# FOC_Lite.net
KiCad netlist of a schematic drawn in Altium Designer
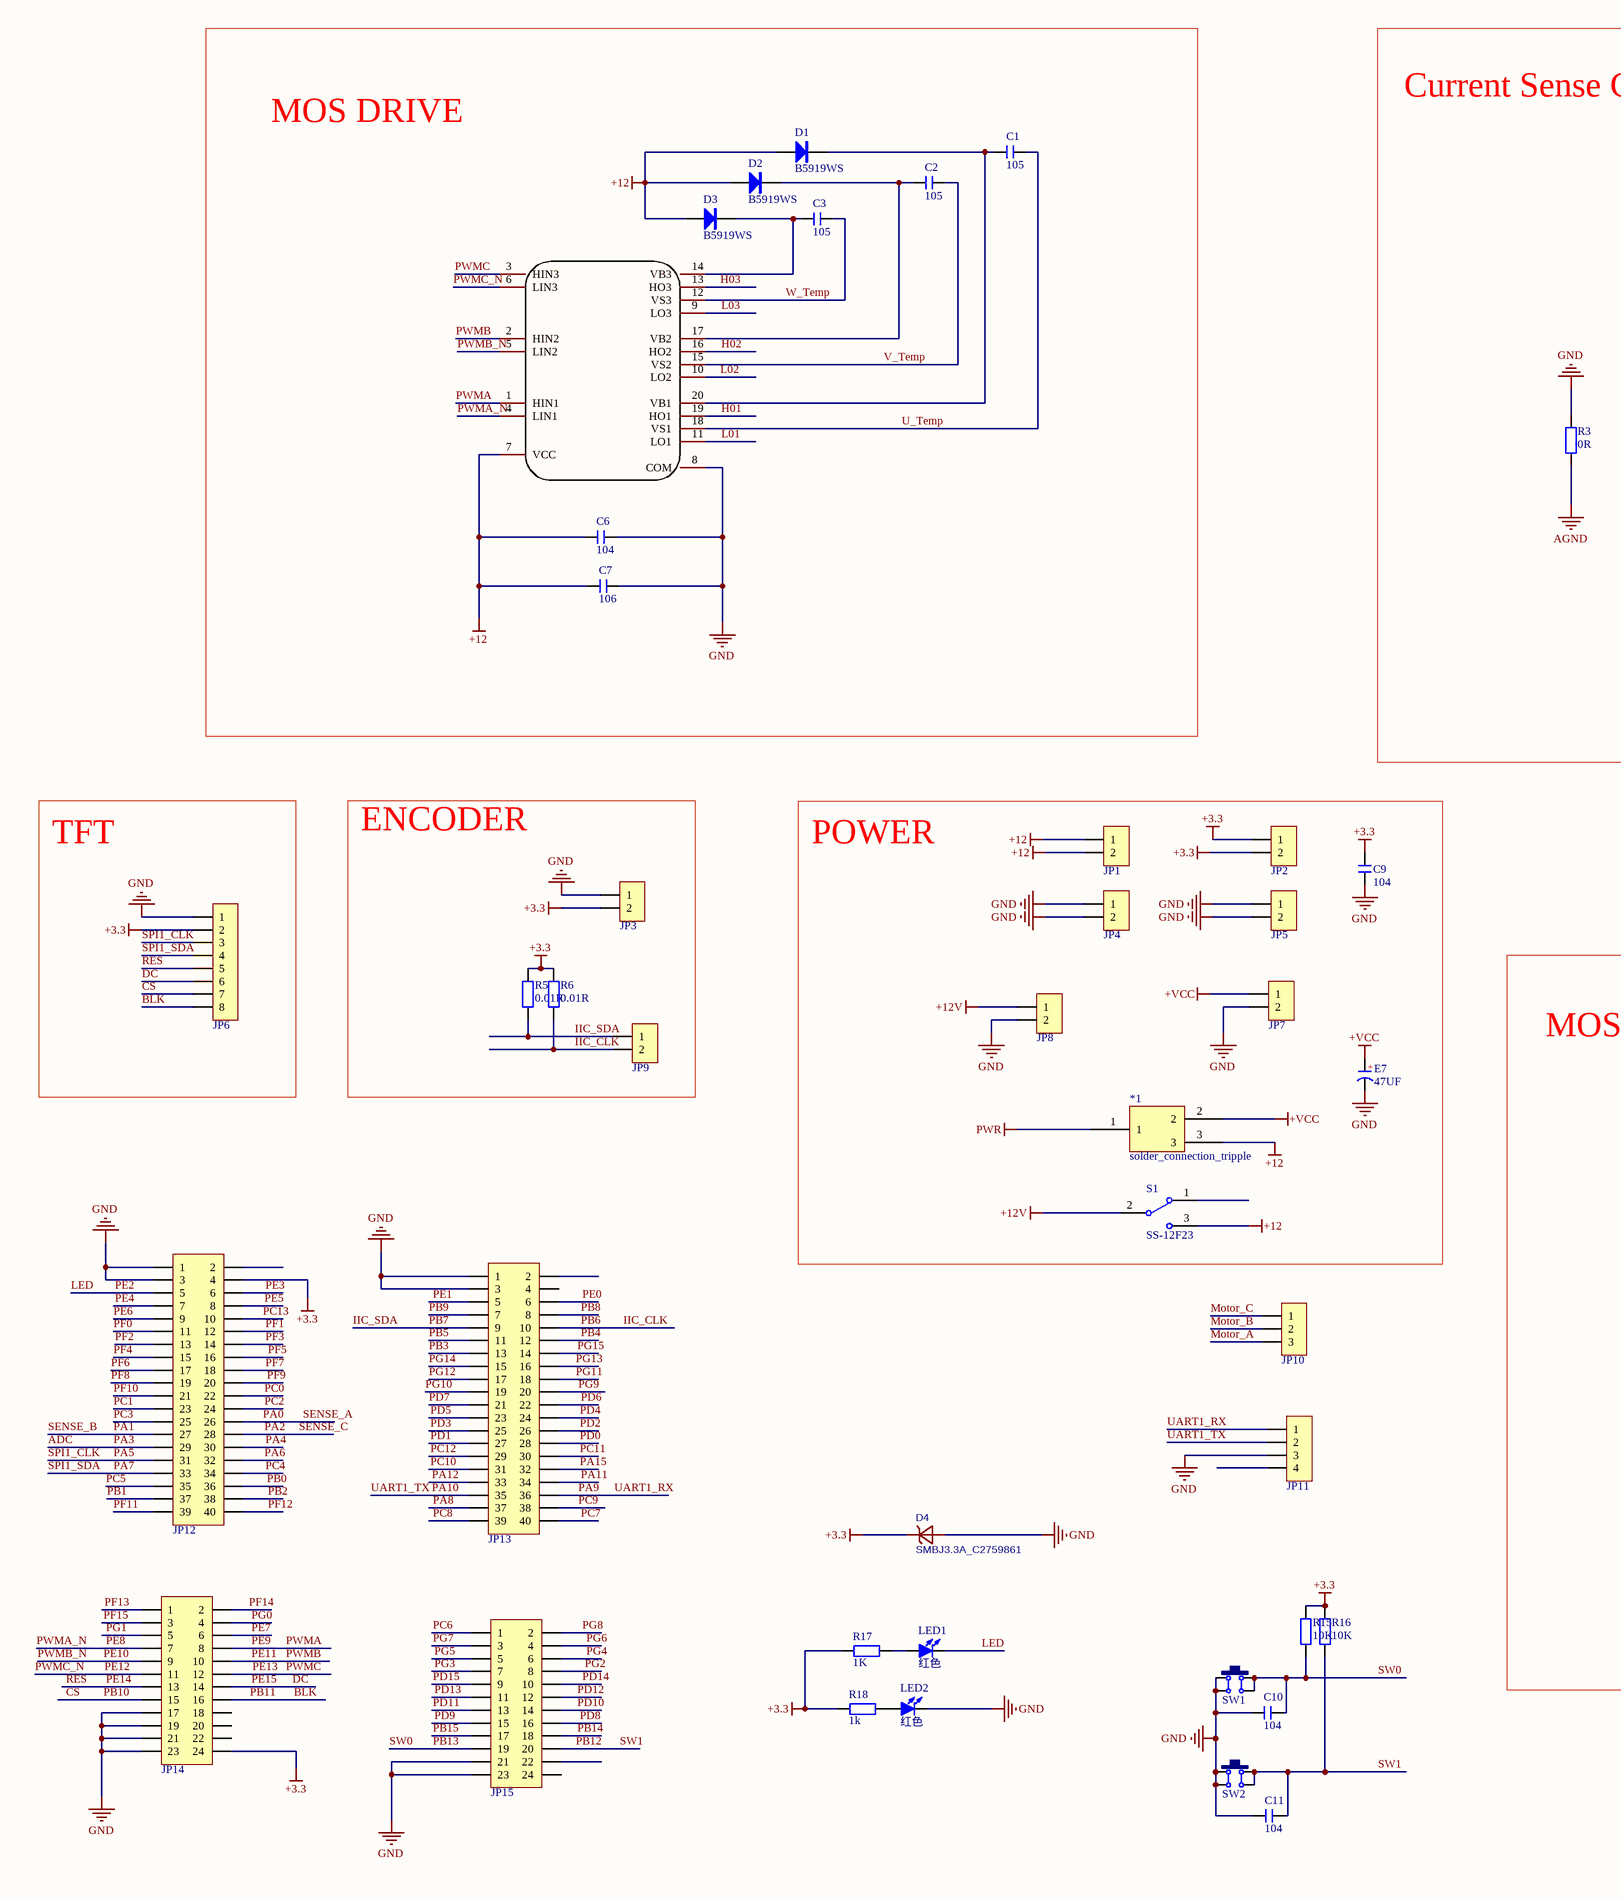
[diagram p0: FOC_Lite.SchDoc, left]
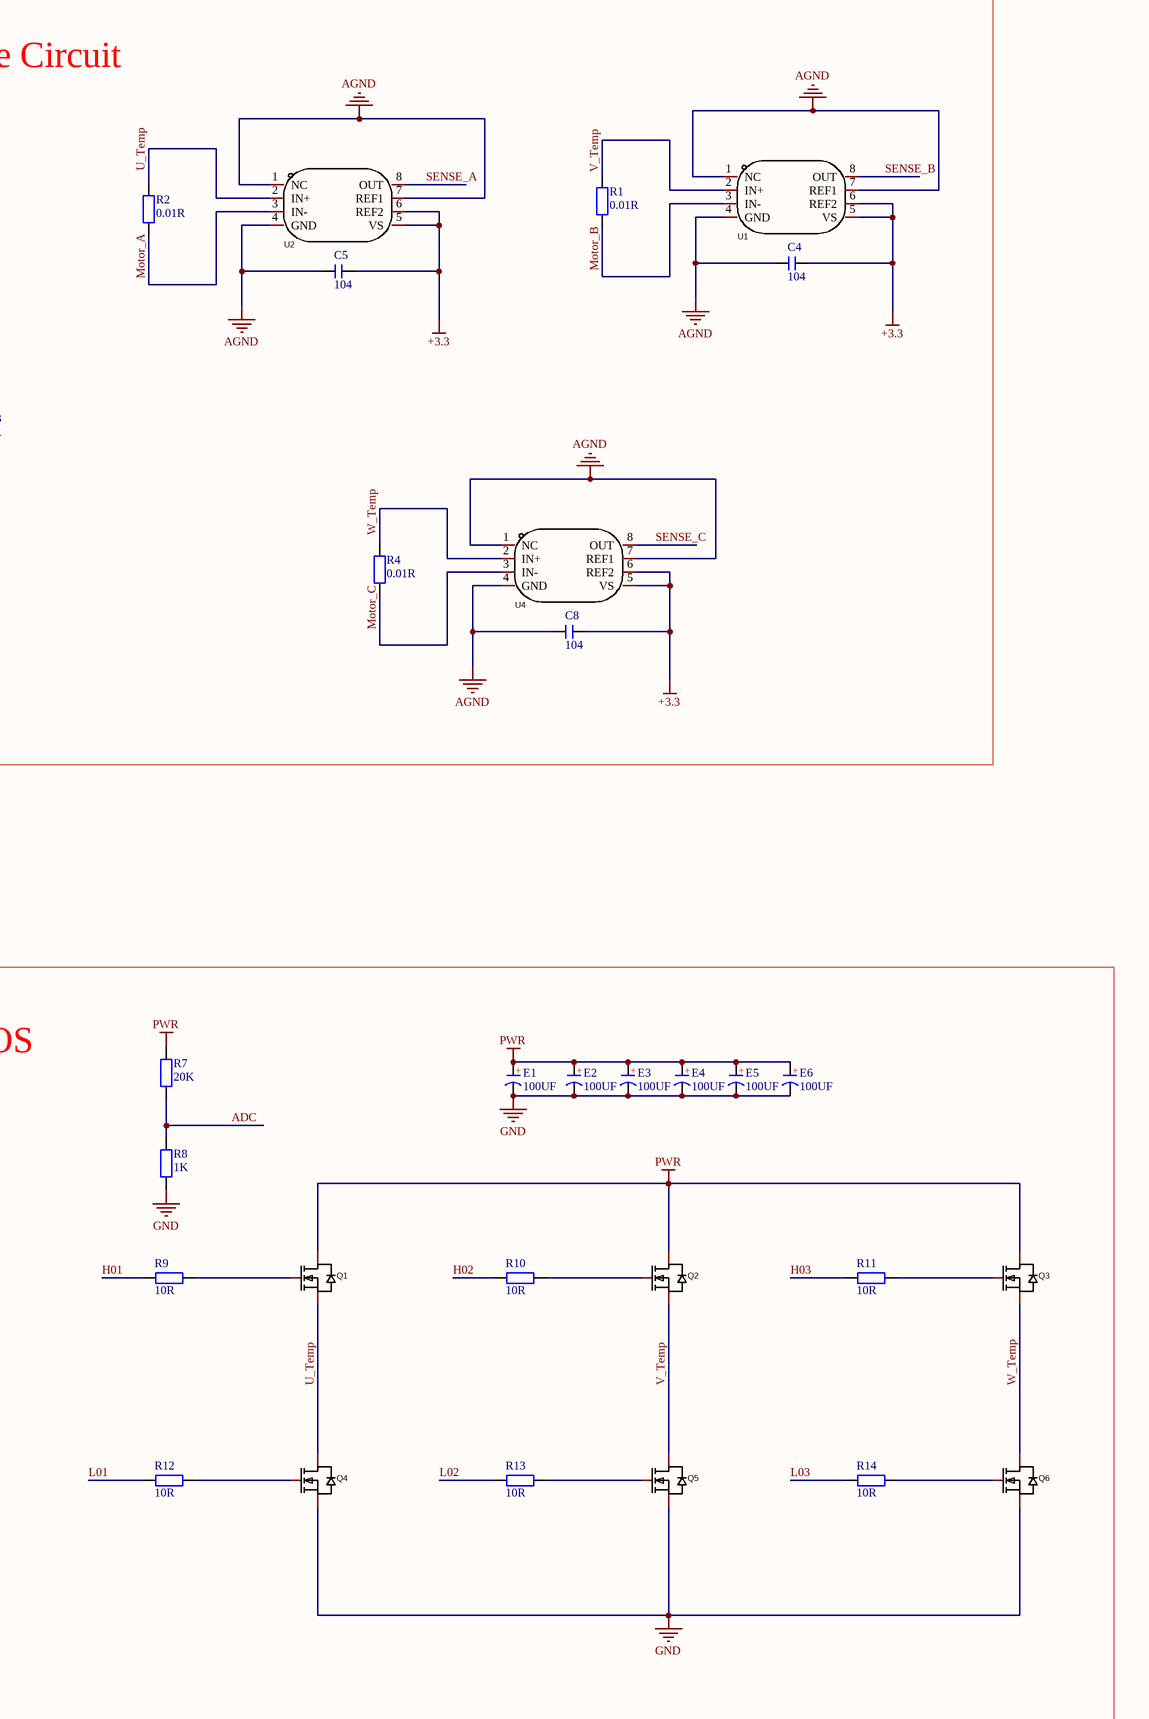
[diagram p1: FOC_Lite.SchDoc, right]

(export (version "E")
  (design (tool "Eeschema 10.0.6"))
  (components
    (comp (ref "*1")
      (value "solder_connection_tripple")
      (footprint "solder_connection_tripple_big")
      (libsource (lib "常见模块2") (part "solder_connection_tripple"))
    )
    (comp (ref "C1")
      (value "105")
      (footprint "C 0805")
      (description "无极性贴片电容")
      (fields (field (name "版权归属") "黎明电子style"))
      (libsource (lib "1.3.2-电阻_电容_电感") (part "C"))
    )
    (comp (ref "C2")
      (value "105")
      (footprint "C 0805")
      (description "无极性贴片电容")
      (fields (field (name "版权归属") "黎明电子style"))
      (libsource (lib "1.3.2-电阻_电容_电感") (part "C"))
    )
    (comp (ref "C3")
      (value "105")
      (footprint "C 0805")
      (description "无极性贴片电容")
      (fields (field (name "版权归属") "黎明电子style"))
      (libsource (lib "1.3.2-电阻_电容_电感") (part "C"))
    )
    (comp (ref "C4")
      (value "104")
      (footprint "C 0805")
      (description "无极性贴片电容")
      (fields (field (name "版权归属") "黎明电子style"))
      (libsource (lib "1.3.2-电阻_电容_电感") (part "C"))
    )
    (comp (ref "C5")
      (value "104")
      (footprint "C 0805")
      (description "无极性贴片电容")
      (fields (field (name "版权归属") "黎明电子style"))
      (libsource (lib "1.3.2-电阻_电容_电感") (part "C"))
    )
    (comp (ref "C6")
      (value "104")
      (footprint "C 0805")
      (description "无极性贴片电容")
      (fields (field (name "版权归属") "黎明电子style"))
      (libsource (lib "1.3.2-电阻_电容_电感") (part "C"))
    )
    (comp (ref "C7")
      (value "106")
      (footprint "C 0805")
      (description "无极性贴片电容")
      (fields (field (name "版权归属") "黎明电子style"))
      (libsource (lib "1.3.2-电阻_电容_电感") (part "C"))
    )
    (comp (ref "C8")
      (value "104")
      (footprint "C 0805")
      (description "无极性贴片电容")
      (fields (field (name "版权归属") "黎明电子style"))
      (libsource (lib "1.3.2-电阻_电容_电感") (part "C"))
    )
    (comp (ref "C9")
      (value "104")
      (footprint "C 0805")
      (description "无极性贴片电容")
      (fields (field (name "版权归属") "黎明电子style"))
      (libsource (lib "1.3.2-电阻_电容_电感") (part "C"))
    )
    (comp (ref "C10")
      (value "104")
      (footprint "C 0603")
      (description "无极性贴片电容")
      (fields (field (name "版权归属") "黎明电子style"))
      (libsource (lib "1.3.2-电阻_电容_电感") (part "C"))
    )
    (comp (ref "C11")
      (value "104")
      (footprint "C 0603")
      (description "无极性贴片电容")
      (fields (field (name "版权归属") "黎明电子style"))
      (libsource (lib "1.3.2-电阻_电容_电感") (part "C"))
    )
    (comp (ref "D1")
      (value "B5919WS")
      (footprint "SOD-323")
      (description "肖特基二极管")
      (fields (field (name "版权归属") "源创客"))
      (libsource (lib "1.3.3-二极管_整流桥") (part "1N5819"))
    )
    (comp (ref "D2")
      (value "B5919WS")
      (footprint "SOD-323")
      (description "肖特基二极管")
      (fields (field (name "版权归属") "源创客"))
      (libsource (lib "1.3.3-二极管_整流桥") (part "1N5819"))
    )
    (comp (ref "D3")
      (value "B5919WS")
      (footprint "SOD-323")
      (description "肖特基二极管")
      (fields (field (name "版权归属") "源创客"))
      (libsource (lib "1.3.3-二极管_整流桥") (part "1N5819"))
    )
    (comp (ref "D4")
      (value "SMBJ3.3A_C2759861")
      (footprint "SMB3.3A")
      (fields
        (field (name "BOM_SUPPLIER PART") "C2759861")
        (field (name "BOM_MANUFACTURER PART") "SMBJ3.3A")
        (field (name "CONTRIBUTOR") "LCSC")
      )
      (libsource (lib "常见模块") (part "SMBJ3.3A_C2759861"))
    )
    (comp (ref "E1")
      (value "100UF")
      (footprint "CD D(7343)")
      (description "贴片钽电容")
      (fields (field (name "版权归属") "黎明电子style"))
      (libsource (lib "1.3.2-电阻_电容_电感") (part "C-CD"))
    )
    (comp (ref "E2")
      (value "100UF")
      (footprint "CD D(7343)")
      (description "贴片钽电容")
      (fields (field (name "版权归属") "黎明电子style"))
      (libsource (lib "1.3.2-电阻_电容_电感") (part "C-CD"))
    )
    (comp (ref "E3")
      (value "100UF")
      (footprint "CD D(7343)")
      (description "贴片钽电容")
      (fields (field (name "版权归属") "黎明电子style"))
      (libsource (lib "1.3.2-电阻_电容_电感") (part "C-CD"))
    )
    (comp (ref "E4")
      (value "100UF")
      (footprint "CD D(7343)")
      (description "贴片钽电容")
      (fields (field (name "版权归属") "黎明电子style"))
      (libsource (lib "1.3.2-电阻_电容_电感") (part "C-CD"))
    )
    (comp (ref "E5")
      (value "100UF")
      (footprint "CD D(7343)")
      (description "贴片钽电容")
      (fields (field (name "版权归属") "黎明电子style"))
      (libsource (lib "1.3.2-电阻_电容_电感") (part "C-CD"))
    )
    (comp (ref "E6")
      (value "100UF")
      (footprint "CD D(7343)")
      (description "贴片钽电容")
      (fields (field (name "版权归属") "黎明电子style"))
      (libsource (lib "1.3.2-电阻_电容_电感") (part "C-CD"))
    )
    (comp (ref "E7")
      (value "47UF")
      (footprint "CD D(7343)")
      (description "贴片钽电容")
      (fields (field (name "版权归属") "黎明电子style"))
      (libsource (lib "1.3.2-电阻_电容_电感") (part "C-CD"))
    )
    (comp (ref "JP1")
      (value "HDR-1X2")
      (footprint "HDR-1X2")
      (description "2P接插件")
      (fields (field (name "版权归属") "黎明电子style"))
      (libsource (lib "1.5.1-接插件") (part "Header 2"))
    )
    (comp (ref "JP2")
      (value "HDR-1X2")
      (footprint "HDR-1X2")
      (description "2P接插件")
      (fields (field (name "版权归属") "黎明电子style"))
      (libsource (lib "1.5.1-接插件") (part "Header 2"))
    )
    (comp (ref "JP3")
      (value "HDR-1X2")
      (footprint "HDR-1X2")
      (description "2P接插件")
      (fields (field (name "版权归属") "黎明电子style"))
      (libsource (lib "1.5.1-接插件") (part "Header 2"))
    )
    (comp (ref "JP4")
      (value "HDR-1X2")
      (footprint "HDR-1X2")
      (description "2P接插件")
      (fields (field (name "版权归属") "黎明电子style"))
      (libsource (lib "1.5.1-接插件") (part "Header 2"))
    )
    (comp (ref "JP5")
      (value "HDR-1X2")
      (footprint "HDR-1X2")
      (description "2P接插件")
      (fields (field (name "版权归属") "黎明电子style"))
      (libsource (lib "1.5.1-接插件") (part "Header 2"))
    )
    (comp (ref "JP6")
      (value "HDR-1X8")
      (footprint "HDR-1X8")
      (description "8P接插件")
      (fields (field (name "版权归属") "黎明电子style"))
      (libsource (lib "1.5.1-接插件") (part "Header 8"))
    )
    (comp (ref "JP7")
      (value "HDR-1X2")
      (footprint "KF128-5.08-2P")
      (description "2P接插件")
      (fields (field (name "版权归属") "黎明电子style"))
      (libsource (lib "1.5.1-接插件") (part "Header 2"))
    )
    (comp (ref "JP8")
      (value "HDR-1X2")
      (footprint "KF128-5.08-2P")
      (description "2P接插件")
      (fields (field (name "版权归属") "黎明电子style"))
      (libsource (lib "1.5.1-接插件") (part "Header 2"))
    )
    (comp (ref "JP9")
      (value "HDR-1X2")
      (footprint "HDR-1X2")
      (description "2P接插件")
      (fields (field (name "版权归属") "黎明电子style"))
      (libsource (lib "1.5.1-接插件") (part "Header 2"))
    )
    (comp (ref "JP10")
      (value "HDR-1X3")
      (footprint "KF128-5.08-3P")
      (description "3P接插件")
      (fields (field (name "版权归属") "黎明电子style"))
      (libsource (lib "1.5.1-接插件") (part "Header 3"))
    )
    (comp (ref "JP11")
      (value "HDR-1X4")
      (footprint "XH2.54-4P")
      (description "4P接插件")
      (fields (field (name "版权归属") "黎明电子style"))
      (libsource (lib "1.5.1-接插件") (part "Header 4"))
    )
    (comp (ref "JP12")
      (value "Header 2X11")
      (footprint "HDR-20X2")
      (description "20*2P接插件")
      (fields (field (name "版权归属") "黎明电子style"))
      (libsource (lib "1.5.1-接插件") (part "Header 20X2"))
    )
    (comp (ref "JP13")
      (value "Header 2X11")
      (footprint "HDR-20X2")
      (description "20*2P接插件")
      (fields (field (name "版权归属") "黎明电子style"))
      (libsource (lib "1.5.1-接插件") (part "Header 20X2"))
    )
    (comp (ref "JP14")
      (value "Header 2X11")
      (footprint "HDR-12X2")
      (description "12*2P接插件")
      (fields (field (name "版权归属") "黎明电子style"))
      (libsource (lib "1.5.1-接插件") (part "Header 12X2"))
    )
    (comp (ref "JP15")
      (value "Header 2X11")
      (footprint "HDR-12X2")
      (description "12*2P接插件")
      (fields (field (name "版权归属") "黎明电子style"))
      (libsource (lib "1.5.1-接插件") (part "Header 12X2"))
    )
    (comp (ref "LED1")
      (value "红色")
      (footprint "LED 0603W")
      (description "贴片LED")
      (libsource (lib "0.3 - LED发光二极管") (part "LED-SMD"))
    )
    (comp (ref "LED2")
      (value "红色")
      (footprint "LED 0603W")
      (description "贴片LED")
      (fields (field (name "版权归属") "黎明电子style"))
      (libsource (lib "1.3.1-LED") (part "LED-SMD"))
    )
    (comp (ref "Q1")
      (value "NCE6080K")
      (footprint "TO-252-2_L6.6-W6.1-P4.57-LS10.1-BR-CW")
      (fields (field (name "MANUFACTURER") "NCE(无锡新洁能)"))
      (libsource (lib "常见模块2") (part "NCE6080K"))
    )
    (comp (ref "Q2")
      (value "NCE6080K")
      (footprint "TO-252-2_L6.6-W6.1-P4.57-LS10.1-BR-CW")
      (fields (field (name "MANUFACTURER") "NCE(无锡新洁能)"))
      (libsource (lib "常见模块2") (part "NCE6080K"))
    )
    (comp (ref "Q3")
      (value "NCE6080K")
      (footprint "TO-252-2_L6.6-W6.1-P4.57-LS10.1-BR-CW")
      (fields (field (name "MANUFACTURER") "NCE(无锡新洁能)"))
      (libsource (lib "常见模块2") (part "NCE6080K"))
    )
    (comp (ref "Q4")
      (value "NCE6080K")
      (footprint "TO-252-2_L6.6-W6.1-P4.57-LS10.1-BR-CW")
      (fields (field (name "MANUFACTURER") "NCE(无锡新洁能)"))
      (libsource (lib "常见模块2") (part "NCE6080K"))
    )
    (comp (ref "Q5")
      (value "NCE6080K")
      (footprint "TO-252-2_L6.6-W6.1-P4.57-LS10.1-BR-CW")
      (fields (field (name "MANUFACTURER") "NCE(无锡新洁能)"))
      (libsource (lib "常见模块2") (part "NCE6080K"))
    )
    (comp (ref "Q6")
      (value "NCE6080K")
      (footprint "TO-252-2_L6.6-W6.1-P4.57-LS10.1-BR-CW")
      (fields (field (name "MANUFACTURER") "NCE(无锡新洁能)"))
      (libsource (lib "常见模块2") (part "NCE6080K"))
    )
    (comp (ref "R1")
      (value "0.01R")
      (footprint "R 2512")
      (description "贴片电阻")
      (fields (field (name "版权归属") "黎明电子style"))
      (libsource (lib "1.3.2-电阻_电容_电感") (part "R"))
    )
    (comp (ref "R2")
      (value "0.01R")
      (footprint "R 2512")
      (description "贴片电阻")
      (fields (field (name "版权归属") "黎明电子style"))
      (libsource (lib "1.3.2-电阻_电容_电感") (part "R"))
    )
    (comp (ref "R3")
      (value "0R")
      (footprint "R 0805")
      (description "贴片电阻")
      (fields (field (name "版权归属") "黎明电子style"))
      (libsource (lib "1.3.2-电阻_电容_电感") (part "R"))
    )
    (comp (ref "R4")
      (value "0.01R")
      (footprint "R 2512")
      (description "贴片电阻")
      (fields (field (name "版权归属") "黎明电子style"))
      (libsource (lib "1.3.2-电阻_电容_电感") (part "R"))
    )
    (comp (ref "R5")
      (value "0.01R")
      (footprint "R 0603")
      (description "贴片电阻")
      (fields (field (name "版权归属") "黎明电子style"))
      (libsource (lib "1.3.2-电阻_电容_电感") (part "R"))
    )
    (comp (ref "R6")
      (value "0.01R")
      (footprint "R 0603")
      (description "贴片电阻")
      (fields (field (name "版权归属") "黎明电子style"))
      (libsource (lib "1.3.2-电阻_电容_电感") (part "R"))
    )
    (comp (ref "R7")
      (value "20K")
      (footprint "R 0603")
      (description "贴片电阻")
      (fields (field (name "版权归属") "黎明电子style"))
      (libsource (lib "1.3.2-电阻_电容_电感") (part "R"))
    )
    (comp (ref "R8")
      (value "1K")
      (footprint "R 0603")
      (description "贴片电阻")
      (fields (field (name "版权归属") "黎明电子style"))
      (libsource (lib "1.3.2-电阻_电容_电感") (part "R"))
    )
    (comp (ref "R9")
      (value "10R")
      (footprint "R 2512")
      (description "贴片电阻")
      (fields (field (name "版权归属") "黎明电子style"))
      (libsource (lib "1.3.2-电阻_电容_电感") (part "R"))
    )
    (comp (ref "R10")
      (value "10R")
      (footprint "R 2512")
      (description "贴片电阻")
      (fields (field (name "版权归属") "黎明电子style"))
      (libsource (lib "1.3.2-电阻_电容_电感") (part "R"))
    )
    (comp (ref "R11")
      (value "10R")
      (footprint "R 2512")
      (description "贴片电阻")
      (fields (field (name "版权归属") "黎明电子style"))
      (libsource (lib "1.3.2-电阻_电容_电感") (part "R"))
    )
    (comp (ref "R12")
      (value "10R")
      (footprint "R 2512")
      (description "贴片电阻")
      (fields (field (name "版权归属") "黎明电子style"))
      (libsource (lib "1.3.2-电阻_电容_电感") (part "R"))
    )
    (comp (ref "R13")
      (value "10R")
      (footprint "R 2512")
      (description "贴片电阻")
      (fields (field (name "版权归属") "黎明电子style"))
      (libsource (lib "1.3.2-电阻_电容_电感") (part "R"))
    )
    (comp (ref "R14")
      (value "10R")
      (footprint "R 2512")
      (description "贴片电阻")
      (fields (field (name "版权归属") "黎明电子style"))
      (libsource (lib "1.3.2-电阻_电容_电感") (part "R"))
    )
    (comp (ref "R15")
      (value "10K")
      (footprint "R 0603")
      (description "贴片电阻")
      (fields (field (name "版权归属") "黎明电子style"))
      (libsource (lib "1.3.2-电阻_电容_电感") (part "R"))
    )
    (comp (ref "R16")
      (value "10K")
      (footprint "R 0603")
      (description "贴片电阻")
      (fields (field (name "版权归属") "黎明电子style"))
      (libsource (lib "1.3.2-电阻_电容_电感") (part "R"))
    )
    (comp (ref "R17")
      (value "1K")
      (footprint "R 0603")
      (description "贴片电阻")
      (fields (field (name "版权归属") "黎明电子style"))
      (libsource (lib "1.3.2-电阻_电容_电感") (part "R"))
    )
    (comp (ref "R18")
      (value "1k")
      (footprint "R 0603")
      (description "贴片电阻")
      (fields (field (name "版权归属") "黎明电子style"))
      (libsource (lib "1.3.2-电阻_电容_电感") (part "R"))
    )
    (comp (ref "S1")
      (value "SS-12F23")
      (footprint "SS12D10")
      (description "1路波动开关")
      (fields (field (name "版权归属") "黎明电子style"))
      (libsource (lib "1.4.1-按键-开关") (part "SSW-1P"))
    )
    (comp (ref "SW1")
      (value "6x6x5")
      (footprint "TSW DIP-6*6*6")
      (description "直插6x6轻触开关")
      (fields (field (name "版权归属") "黎明电子style"))
      (libsource (lib "1.4.1-按键-开关") (part "TSW DIP-6x6"))
    )
    (comp (ref "SW2")
      (value "6x6x5")
      (footprint "TSW DIP-6*6*6")
      (description "直插6x6轻触开关")
      (fields (field (name "版权归属") "黎明电子style"))
      (libsource (lib "1.4.1-按键-开关") (part "TSW DIP-6x6"))
    )
    (comp (ref "U1")
      (value "INA240A2PWR")
      (footprint "TSSOP-8_L4.4-W3.0-P0.65-LS6.4-BL")
      (fields (field (name "MANUFACTURER") "TI(德州仪器)"))
      (libsource (lib "常见模块2") (part "INA240A2PWR"))
    )
    (comp (ref "U2")
      (value "INA240A2PWR")
      (footprint "TSSOP-8_L4.4-W3.0-P0.65-LS6.4-BL")
      (fields (field (name "MANUFACTURER") "TI(德州仪器)"))
      (libsource (lib "常见模块2") (part "INA240A2PWR"))
    )
    (comp (ref "U3")
      (value "FD6288T")
      (footprint "FD6288T")
      (fields (field (name "MANUFACTURER") "Fortior Tech(峰岹)"))
      (libsource (lib "常见模块2") (part "FD6288T"))
    )
    (comp (ref "U4")
      (value "INA240A2PWR")
      (footprint "TSSOP-8_L4.4-W3.0-P0.65-LS6.4-BL")
      (fields (field (name "MANUFACTURER") "TI(德州仪器)"))
      (libsource (lib "常见模块2") (part "INA240A2PWR"))
    )
  )
  (nets
    (net (code "1") (name "+3.3") (class "Default")
      (node (ref "C4") (pin "2") (pinfunction "2_2") (pintype "passive"))
      (node (ref "C5") (pin "2") (pinfunction "2_2") (pintype "passive"))
      (node (ref "C8") (pin "2") (pinfunction "2_2") (pintype "passive"))
      (node (ref "C9") (pin "2") (pinfunction "2_2") (pintype "passive"))
      (node (ref "D4") (pin "1") (pinfunction "1_1") (pintype "passive"))
      (node (ref "JP12") (pin "4") (pinfunction "4_4") (pintype "passive"))
      (node (ref "JP14") (pin "24") (pinfunction "24_24") (pintype "passive"))
      (node (ref "JP2") (pin "1") (pinfunction "1_1") (pintype "passive"))
      (node (ref "JP2") (pin "2") (pinfunction "2_2") (pintype "passive"))
      (node (ref "JP3") (pin "2") (pinfunction "2_2") (pintype "passive"))
      (node (ref "JP6") (pin "2") (pinfunction "2_2") (pintype "passive"))
      (node (ref "R15") (pin "1") (pinfunction "1_1") (pintype "passive"))
      (node (ref "R16") (pin "1") (pinfunction "1_1") (pintype "passive"))
      (node (ref "R17") (pin "2") (pinfunction "2_2") (pintype "passive"))
      (node (ref "R18") (pin "1") (pinfunction "1_1") (pintype "passive"))
      (node (ref "R5") (pin "2") (pinfunction "2_2") (pintype "passive"))
      (node (ref "R6") (pin "2") (pinfunction "2_2") (pintype "passive"))
      (node (ref "U1") (pin "5") (pinfunction "VS_5") (pintype "passive"))
      (node (ref "U1") (pin "6") (pinfunction "REF2_6") (pintype "passive"))
      (node (ref "U2") (pin "5") (pinfunction "VS_5") (pintype "passive"))
      (node (ref "U2") (pin "6") (pinfunction "REF2_6") (pintype "passive"))
      (node (ref "U4") (pin "5") (pinfunction "VS_5") (pintype "passive"))
      (node (ref "U4") (pin "6") (pinfunction "REF2_6") (pintype "passive"))
    )
    (net (code "2") (name "+12") (class "Default")
      (node (ref "*1") (pin "3") (pinfunction "3_3") (pintype "passive"))
      (node (ref "C6") (pin "1") (pinfunction "1_1") (pintype "passive"))
      (node (ref "C7") (pin "1") (pinfunction "1_1") (pintype "passive"))
      (node (ref "D1") (pin "1") (pinfunction "A_1") (pintype "passive"))
      (node (ref "D2") (pin "1") (pinfunction "A_1") (pintype "passive"))
      (node (ref "D3") (pin "1") (pinfunction "A_1") (pintype "passive"))
      (node (ref "JP1") (pin "1") (pinfunction "1_1") (pintype "passive"))
      (node (ref "JP1") (pin "2") (pinfunction "2_2") (pintype "passive"))
      (node (ref "S1") (pin "3") (pinfunction "3_3") (pintype "passive"))
      (node (ref "U3") (pin "7") (pinfunction "VCC_7") (pintype "passive"))
    )
    (net (code "3") (name "+12V") (class "Default")
      (node (ref "JP8") (pin "1") (pinfunction "1_1") (pintype "passive"))
      (node (ref "S1") (pin "2") (pinfunction "2_2") (pintype "passive"))
    )
    (net (code "4") (name "+VCC") (class "Default")
      (node (ref "*1") (pin "2") (pinfunction "2_2") (pintype "passive"))
      (node (ref "E7") (pin "1") (pinfunction "A_1") (pintype "passive"))
      (node (ref "JP7") (pin "1") (pinfunction "1_1") (pintype "passive"))
    )
    (net (code "5") (name "/ADC") (class "Default")
      (node (ref "JP12") (pin "29") (pinfunction "29_29") (pintype "passive"))
      (node (ref "R7") (pin "2") (pinfunction "2_2") (pintype "passive"))
      (node (ref "R8") (pin "1") (pinfunction "1_1") (pintype "passive"))
    )
    (net (code "6") (name "/BLK") (class "Default")
      (node (ref "JP14") (pin "16") (pinfunction "16_16") (pintype "passive"))
      (node (ref "JP6") (pin "8") (pinfunction "8_8") (pintype "passive"))
    )
    (net (code "7") (name "/CS") (class "Default")
      (node (ref "JP14") (pin "15") (pinfunction "15_15") (pintype "passive"))
      (node (ref "JP6") (pin "7") (pinfunction "7_7") (pintype "passive"))
    )
    (net (code "8") (name "/DC") (class "Default")
      (node (ref "JP14") (pin "14") (pinfunction "14_14") (pintype "passive"))
      (node (ref "JP6") (pin "6") (pinfunction "6_6") (pintype "passive"))
    )
    (net (code "9") (name "/H01") (class "Default")
      (node (ref "R9") (pin "2") (pinfunction "2_2") (pintype "passive"))
      (node (ref "U3") (pin "19") (pinfunction "HO1_19") (pintype "passive"))
    )
    (net (code "10") (name "/H02") (class "Default")
      (node (ref "R10") (pin "2") (pinfunction "2_2") (pintype "passive"))
      (node (ref "U3") (pin "16") (pinfunction "HO2_16") (pintype "passive"))
    )
    (net (code "11") (name "/H03") (class "Default")
      (node (ref "R11") (pin "2") (pinfunction "2_2") (pintype "passive"))
      (node (ref "U3") (pin "13") (pinfunction "HO3_13") (pintype "passive"))
    )
    (net (code "12") (name "/IIC_CLK") (class "Default")
      (node (ref "JP13") (pin "10") (pinfunction "10_10") (pintype "passive"))
      (node (ref "JP9") (pin "2") (pinfunction "2_2") (pintype "passive"))
      (node (ref "R6") (pin "1") (pinfunction "1_1") (pintype "passive"))
    )
    (net (code "13") (name "/IIC_SDA") (class "Default")
      (node (ref "JP13") (pin "9") (pinfunction "9_9") (pintype "passive"))
      (node (ref "JP9") (pin "1") (pinfunction "1_1") (pintype "passive"))
      (node (ref "R5") (pin "1") (pinfunction "1_1") (pintype "passive"))
    )
    (net (code "14") (name "/L01") (class "Default")
      (node (ref "R12") (pin "2") (pinfunction "2_2") (pintype "passive"))
      (node (ref "U3") (pin "11") (pinfunction "LO1_11") (pintype "passive"))
    )
    (net (code "15") (name "/L02") (class "Default")
      (node (ref "R13") (pin "2") (pinfunction "2_2") (pintype "passive"))
      (node (ref "U3") (pin "10") (pinfunction "LO2_10") (pintype "passive"))
    )
    (net (code "16") (name "/L03") (class "Default")
      (node (ref "R14") (pin "2") (pinfunction "2_2") (pintype "passive"))
      (node (ref "U3") (pin "9") (pinfunction "LO3_9") (pintype "passive"))
    )
    (net (code "17") (name "/LED") (class "Default")
      (node (ref "JP12") (pin "5") (pinfunction "5_5") (pintype "passive"))
      (node (ref "LED1") (pin "2") (pinfunction "K_2") (pintype "passive"))
    )
    (net (code "18") (name "/Motor_A") (class "Default")
      (node (ref "JP10") (pin "3") (pinfunction "3_3") (pintype "passive"))
      (node (ref "R2") (pin "1") (pinfunction "1_1") (pintype "passive"))
      (node (ref "U2") (pin "3") (pinfunction "IN-_3") (pintype "passive"))
    )
    (net (code "19") (name "/Motor_B") (class "Default")
      (node (ref "JP10") (pin "2") (pinfunction "2_2") (pintype "passive"))
      (node (ref "R1") (pin "1") (pinfunction "1_1") (pintype "passive"))
      (node (ref "U1") (pin "3") (pinfunction "IN-_3") (pintype "passive"))
    )
    (net (code "20") (name "/Motor_C") (class "Default")
      (node (ref "JP10") (pin "1") (pinfunction "1_1") (pintype "passive"))
      (node (ref "R4") (pin "1") (pinfunction "1_1") (pintype "passive"))
      (node (ref "U4") (pin "3") (pinfunction "IN-_3") (pintype "passive"))
    )
    (net (code "21") (name "/PA0") (class "Default")
      (node (ref "JP12") (pin "26") (pinfunction "26_26") (pintype "passive"))
      (node (ref "U2") (pin "8") (pinfunction "OUT_8") (pintype "passive"))
    )
    (net (code "22") (name "/PA1") (class "Default")
      (node (ref "JP12") (pin "27") (pinfunction "27_27") (pintype "passive"))
      (node (ref "U1") (pin "8") (pinfunction "OUT_8") (pintype "passive"))
    )
    (net (code "23") (name "/PA2") (class "Default")
      (node (ref "JP12") (pin "28") (pinfunction "28_28") (pintype "passive"))
      (node (ref "U4") (pin "8") (pinfunction "OUT_8") (pintype "passive"))
    )
    (net (code "24") (name "/PA4") (class "Default")
      (node (ref "JP12") (pin "30") (pinfunction "30_30") (pintype "passive"))
    )
    (net (code "25") (name "/PA5") (class "Default")
      (node (ref "JP12") (pin "31") (pinfunction "31_31") (pintype "passive"))
      (node (ref "JP6") (pin "3") (pinfunction "3_3") (pintype "passive"))
    )
    (net (code "26") (name "/PA6") (class "Default")
      (node (ref "JP12") (pin "32") (pinfunction "32_32") (pintype "passive"))
    )
    (net (code "27") (name "/PA7") (class "Default")
      (node (ref "JP12") (pin "33") (pinfunction "33_33") (pintype "passive"))
      (node (ref "JP6") (pin "4") (pinfunction "4_4") (pintype "passive"))
    )
    (net (code "28") (name "/PA8") (class "Default")
      (node (ref "JP13") (pin "37") (pinfunction "37_37") (pintype "passive"))
    )
    (net (code "29") (name "/PA9") (class "Default")
      (node (ref "JP11") (pin "1") (pinfunction "1_1") (pintype "passive"))
      (node (ref "JP13") (pin "36") (pinfunction "36_36") (pintype "passive"))
    )
    (net (code "30") (name "/PA10") (class "Default")
      (node (ref "JP11") (pin "2") (pinfunction "2_2") (pintype "passive"))
      (node (ref "JP13") (pin "35") (pinfunction "35_35") (pintype "passive"))
    )
    (net (code "31") (name "/PA11") (class "Default")
      (node (ref "JP13") (pin "34") (pinfunction "34_34") (pintype "passive"))
    )
    (net (code "32") (name "/PA12") (class "Default")
      (node (ref "JP13") (pin "33") (pinfunction "33_33") (pintype "passive"))
    )
    (net (code "33") (name "/PA15") (class "Default")
      (node (ref "JP13") (pin "32") (pinfunction "32_32") (pintype "passive"))
    )
    (net (code "34") (name "/PB0") (class "Default")
      (node (ref "JP12") (pin "36") (pinfunction "36_36") (pintype "passive"))
    )
    (net (code "35") (name "/PB1") (class "Default")
      (node (ref "JP12") (pin "37") (pinfunction "37_37") (pintype "passive"))
    )
    (net (code "36") (name "/PB2") (class "Default")
      (node (ref "JP12") (pin "38") (pinfunction "38_38") (pintype "passive"))
    )
    (net (code "37") (name "/PB3") (class "Default")
      (node (ref "JP13") (pin "13") (pinfunction "13_13") (pintype "passive"))
    )
    (net (code "38") (name "/PB4") (class "Default")
      (node (ref "JP13") (pin "12") (pinfunction "12_12") (pintype "passive"))
    )
    (net (code "39") (name "/PB5") (class "Default")
      (node (ref "JP13") (pin "11") (pinfunction "11_11") (pintype "passive"))
    )
    (net (code "40") (name "/PB8") (class "Default")
      (node (ref "JP13") (pin "8") (pinfunction "8_8") (pintype "passive"))
    )
    (net (code "41") (name "/PB9") (class "Default")
      (node (ref "JP13") (pin "7") (pinfunction "7_7") (pintype "passive"))
    )
    (net (code "42") (name "/PB12") (class "Default")
      (node (ref "C11") (pin "1") (pinfunction "1_1") (pintype "passive"))
      (node (ref "JP15") (pin "20") (pinfunction "20_20") (pintype "passive"))
      (node (ref "R16") (pin "2") (pinfunction "2_2") (pintype "passive"))
      (node (ref "SW2") (pin "2") (pinfunction "2_2") (pintype "passive"))
      (node (ref "SW2") (pin "3") (pinfunction "3_3") (pintype "passive"))
    )
    (net (code "43") (name "/PB13") (class "Default")
      (node (ref "C10") (pin "1") (pinfunction "1_1") (pintype "passive"))
      (node (ref "JP15") (pin "19") (pinfunction "19_19") (pintype "passive"))
      (node (ref "R15") (pin "2") (pinfunction "2_2") (pintype "passive"))
      (node (ref "SW1") (pin "2") (pinfunction "2_2") (pintype "passive"))
      (node (ref "SW1") (pin "3") (pinfunction "3_3") (pintype "passive"))
    )
    (net (code "44") (name "/PB14") (class "Default")
      (node (ref "JP15") (pin "18") (pinfunction "18_18") (pintype "passive"))
    )
    (net (code "45") (name "/PB15") (class "Default")
      (node (ref "JP15") (pin "17") (pinfunction "17_17") (pintype "passive"))
    )
    (net (code "46") (name "/PC0") (class "Default")
      (node (ref "JP12") (pin "22") (pinfunction "22_22") (pintype "passive"))
    )
    (net (code "47") (name "/PC1") (class "Default")
      (node (ref "JP12") (pin "23") (pinfunction "23_23") (pintype "passive"))
    )
    (net (code "48") (name "/PC2") (class "Default")
      (node (ref "JP12") (pin "24") (pinfunction "24_24") (pintype "passive"))
    )
    (net (code "49") (name "/PC3") (class "Default")
      (node (ref "JP12") (pin "25") (pinfunction "25_25") (pintype "passive"))
    )
    (net (code "50") (name "/PC4") (class "Default")
      (node (ref "JP12") (pin "34") (pinfunction "34_34") (pintype "passive"))
    )
    (net (code "51") (name "/PC5") (class "Default")
      (node (ref "JP12") (pin "35") (pinfunction "35_35") (pintype "passive"))
    )
    (net (code "52") (name "/PC6") (class "Default")
      (node (ref "JP15") (pin "1") (pinfunction "1_1") (pintype "passive"))
    )
    (net (code "53") (name "/PC7") (class "Default")
      (node (ref "JP13") (pin "40") (pinfunction "40_40") (pintype "passive"))
    )
    (net (code "54") (name "/PC8") (class "Default")
      (node (ref "JP13") (pin "39") (pinfunction "39_39") (pintype "passive"))
    )
    (net (code "55") (name "/PC9") (class "Default")
      (node (ref "JP13") (pin "38") (pinfunction "38_38") (pintype "passive"))
    )
    (net (code "56") (name "/PC10") (class "Default")
      (node (ref "JP13") (pin "31") (pinfunction "31_31") (pintype "passive"))
    )
    (net (code "57") (name "/PC11") (class "Default")
      (node (ref "JP13") (pin "30") (pinfunction "30_30") (pintype "passive"))
    )
    (net (code "58") (name "/PC12") (class "Default")
      (node (ref "JP13") (pin "29") (pinfunction "29_29") (pintype "passive"))
    )
    (net (code "59") (name "/PC13") (class "Default")
      (node (ref "JP12") (pin "10") (pinfunction "10_10") (pintype "passive"))
    )
    (net (code "60") (name "/PD0") (class "Default")
      (node (ref "JP13") (pin "28") (pinfunction "28_28") (pintype "passive"))
    )
    (net (code "61") (name "/PD1") (class "Default")
      (node (ref "JP13") (pin "27") (pinfunction "27_27") (pintype "passive"))
    )
    (net (code "62") (name "/PD2") (class "Default")
      (node (ref "JP13") (pin "26") (pinfunction "26_26") (pintype "passive"))
    )
    (net (code "63") (name "/PD3") (class "Default")
      (node (ref "JP13") (pin "25") (pinfunction "25_25") (pintype "passive"))
    )
    (net (code "64") (name "/PD4") (class "Default")
      (node (ref "JP13") (pin "24") (pinfunction "24_24") (pintype "passive"))
    )
    (net (code "65") (name "/PD5") (class "Default")
      (node (ref "JP13") (pin "23") (pinfunction "23_23") (pintype "passive"))
    )
    (net (code "66") (name "/PD6") (class "Default")
      (node (ref "JP13") (pin "22") (pinfunction "22_22") (pintype "passive"))
    )
    (net (code "67") (name "/PD7") (class "Default")
      (node (ref "JP13") (pin "21") (pinfunction "21_21") (pintype "passive"))
    )
    (net (code "68") (name "/PD8") (class "Default")
      (node (ref "JP15") (pin "16") (pinfunction "16_16") (pintype "passive"))
    )
    (net (code "69") (name "/PD9") (class "Default")
      (node (ref "JP15") (pin "15") (pinfunction "15_15") (pintype "passive"))
    )
    (net (code "70") (name "/PD10") (class "Default")
      (node (ref "JP15") (pin "14") (pinfunction "14_14") (pintype "passive"))
    )
    (net (code "71") (name "/PD11") (class "Default")
      (node (ref "JP15") (pin "13") (pinfunction "13_13") (pintype "passive"))
    )
    (net (code "72") (name "/PD12") (class "Default")
      (node (ref "JP15") (pin "12") (pinfunction "12_12") (pintype "passive"))
    )
    (net (code "73") (name "/PD13") (class "Default")
      (node (ref "JP15") (pin "11") (pinfunction "11_11") (pintype "passive"))
    )
    (net (code "74") (name "/PD14") (class "Default")
      (node (ref "JP15") (pin "10") (pinfunction "10_10") (pintype "passive"))
    )
    (net (code "75") (name "/PD15") (class "Default")
      (node (ref "JP15") (pin "9") (pinfunction "9_9") (pintype "passive"))
    )
    (net (code "76") (name "/PE0") (class "Default")
      (node (ref "JP13") (pin "6") (pinfunction "6_6") (pintype "passive"))
    )
    (net (code "77") (name "/PE1") (class "Default")
      (node (ref "JP13") (pin "5") (pinfunction "5_5") (pintype "passive"))
    )
    (net (code "78") (name "/PE3") (class "Default")
      (node (ref "JP12") (pin "6") (pinfunction "6_6") (pintype "passive"))
    )
    (net (code "79") (name "/PE4") (class "Default")
      (node (ref "JP12") (pin "7") (pinfunction "7_7") (pintype "passive"))
    )
    (net (code "80") (name "/PE5") (class "Default")
      (node (ref "JP12") (pin "8") (pinfunction "8_8") (pintype "passive"))
    )
    (net (code "81") (name "/PE6") (class "Default")
      (node (ref "JP12") (pin "9") (pinfunction "9_9") (pintype "passive"))
    )
    (net (code "82") (name "/PE7") (class "Default")
      (node (ref "JP14") (pin "6") (pinfunction "6_6") (pintype "passive"))
    )
    (net (code "83") (name "/PE8") (class "Default")
      (node (ref "JP14") (pin "7") (pinfunction "7_7") (pintype "passive"))
      (node (ref "U3") (pin "4") (pinfunction "LIN1_4") (pintype "passive"))
    )
    (net (code "84") (name "/PE9") (class "Default")
      (node (ref "JP14") (pin "8") (pinfunction "8_8") (pintype "passive"))
      (node (ref "U3") (pin "1") (pinfunction "HIN1_1") (pintype "passive"))
    )
    (net (code "85") (name "/PE10") (class "Default")
      (node (ref "JP14") (pin "9") (pinfunction "9_9") (pintype "passive"))
      (node (ref "U3") (pin "5") (pinfunction "LIN2_5") (pintype "passive"))
    )
    (net (code "86") (name "/PE11") (class "Default")
      (node (ref "JP14") (pin "10") (pinfunction "10_10") (pintype "passive"))
      (node (ref "U3") (pin "2") (pinfunction "HIN2_2") (pintype "passive"))
    )
    (net (code "87") (name "/PE12") (class "Default")
      (node (ref "JP14") (pin "11") (pinfunction "11_11") (pintype "passive"))
      (node (ref "U3") (pin "6") (pinfunction "LIN3_6") (pintype "passive"))
    )
    (net (code "88") (name "/PE13") (class "Default")
      (node (ref "JP14") (pin "12") (pinfunction "12_12") (pintype "passive"))
      (node (ref "U3") (pin "3") (pinfunction "HIN3_3") (pintype "passive"))
    )
    (net (code "89") (name "/PE14") (class "Default")
      (node (ref "JP14") (pin "13") (pinfunction "13_13") (pintype "passive"))
      (node (ref "JP6") (pin "5") (pinfunction "5_5") (pintype "passive"))
    )
    (net (code "90") (name "/PF0") (class "Default")
      (node (ref "JP12") (pin "11") (pinfunction "11_11") (pintype "passive"))
    )
    (net (code "91") (name "/PF1") (class "Default")
      (node (ref "JP12") (pin "12") (pinfunction "12_12") (pintype "passive"))
    )
    (net (code "92") (name "/PF2") (class "Default")
      (node (ref "JP12") (pin "13") (pinfunction "13_13") (pintype "passive"))
    )
    (net (code "93") (name "/PF3") (class "Default")
      (node (ref "JP12") (pin "14") (pinfunction "14_14") (pintype "passive"))
    )
    (net (code "94") (name "/PF4") (class "Default")
      (node (ref "JP12") (pin "15") (pinfunction "15_15") (pintype "passive"))
    )
    (net (code "95") (name "/PF5") (class "Default")
      (node (ref "JP12") (pin "16") (pinfunction "16_16") (pintype "passive"))
    )
    (net (code "96") (name "/PF6") (class "Default")
      (node (ref "JP12") (pin "17") (pinfunction "17_17") (pintype "passive"))
    )
    (net (code "97") (name "/PF7") (class "Default")
      (node (ref "JP12") (pin "18") (pinfunction "18_18") (pintype "passive"))
    )
    (net (code "98") (name "/PF8") (class "Default")
      (node (ref "JP12") (pin "19") (pinfunction "19_19") (pintype "passive"))
    )
    (net (code "99") (name "/PF9") (class "Default")
      (node (ref "JP12") (pin "20") (pinfunction "20_20") (pintype "passive"))
    )
    (net (code "100") (name "/PF10") (class "Default")
      (node (ref "JP12") (pin "21") (pinfunction "21_21") (pintype "passive"))
    )
    (net (code "101") (name "/PF11") (class "Default")
      (node (ref "JP12") (pin "39") (pinfunction "39_39") (pintype "passive"))
    )
    (net (code "102") (name "/PF12") (class "Default")
      (node (ref "JP12") (pin "40") (pinfunction "40_40") (pintype "passive"))
    )
    (net (code "103") (name "/PF13") (class "Default")
      (node (ref "JP14") (pin "1") (pinfunction "1_1") (pintype "passive"))
    )
    (net (code "104") (name "/PF14") (class "Default")
      (node (ref "JP14") (pin "2") (pinfunction "2_2") (pintype "passive"))
    )
    (net (code "105") (name "/PF15") (class "Default")
      (node (ref "JP14") (pin "3") (pinfunction "3_3") (pintype "passive"))
    )
    (net (code "106") (name "/PG0") (class "Default")
      (node (ref "JP14") (pin "4") (pinfunction "4_4") (pintype "passive"))
    )
    (net (code "107") (name "/PG1") (class "Default")
      (node (ref "JP14") (pin "5") (pinfunction "5_5") (pintype "passive"))
    )
    (net (code "108") (name "/PG2") (class "Default")
      (node (ref "JP15") (pin "8") (pinfunction "8_8") (pintype "passive"))
    )
    (net (code "109") (name "/PG3") (class "Default")
      (node (ref "JP15") (pin "7") (pinfunction "7_7") (pintype "passive"))
    )
    (net (code "110") (name "/PG4") (class "Default")
      (node (ref "JP15") (pin "6") (pinfunction "6_6") (pintype "passive"))
    )
    (net (code "111") (name "/PG5") (class "Default")
      (node (ref "JP15") (pin "5") (pinfunction "5_5") (pintype "passive"))
    )
    (net (code "112") (name "/PG6") (class "Default")
      (node (ref "JP15") (pin "4") (pinfunction "4_4") (pintype "passive"))
    )
    (net (code "113") (name "/PG7") (class "Default")
      (node (ref "JP15") (pin "3") (pinfunction "3_3") (pintype "passive"))
    )
    (net (code "114") (name "/PG8") (class "Default")
      (node (ref "JP15") (pin "2") (pinfunction "2_2") (pintype "passive"))
    )
    (net (code "115") (name "/PG9") (class "Default")
      (node (ref "JP13") (pin "20") (pinfunction "20_20") (pintype "passive"))
    )
    (net (code "116") (name "/PG10") (class "Default")
      (node (ref "JP13") (pin "19") (pinfunction "19_19") (pintype "passive"))
    )
    (net (code "117") (name "/PG11") (class "Default")
      (node (ref "JP13") (pin "18") (pinfunction "18_18") (pintype "passive"))
    )
    (net (code "118") (name "/PG12") (class "Default")
      (node (ref "JP13") (pin "17") (pinfunction "17_17") (pintype "passive"))
    )
    (net (code "119") (name "/PG13") (class "Default")
      (node (ref "JP13") (pin "16") (pinfunction "16_16") (pintype "passive"))
    )
    (net (code "120") (name "/PG14") (class "Default")
      (node (ref "JP13") (pin "15") (pinfunction "15_15") (pintype "passive"))
    )
    (net (code "121") (name "/PG15") (class "Default")
      (node (ref "JP13") (pin "14") (pinfunction "14_14") (pintype "passive"))
    )
    (net (code "122") (name "/U_Temp") (class "Default")
      (node (ref "C1") (pin "2") (pinfunction "2_2") (pintype "passive"))
      (node (ref "Q1") (pin "3") (pinfunction "S_3") (pintype "passive"))
      (node (ref "Q4") (pin "2") (pinfunction "D_2") (pintype "passive"))
      (node (ref "R2") (pin "2") (pinfunction "2_2") (pintype "passive"))
      (node (ref "U2") (pin "2") (pinfunction "IN+_2") (pintype "passive"))
      (node (ref "U3") (pin "18") (pinfunction "VS1_18") (pintype "passive"))
    )
    (net (code "123") (name "/V_Temp") (class "Default")
      (node (ref "C2") (pin "2") (pinfunction "2_2") (pintype "passive"))
      (node (ref "Q2") (pin "3") (pinfunction "S_3") (pintype "passive"))
      (node (ref "Q5") (pin "2") (pinfunction "D_2") (pintype "passive"))
      (node (ref "R1") (pin "2") (pinfunction "2_2") (pintype "passive"))
      (node (ref "U1") (pin "2") (pinfunction "IN+_2") (pintype "passive"))
      (node (ref "U3") (pin "15") (pinfunction "VS2_15") (pintype "passive"))
    )
    (net (code "124") (name "/W_Temp") (class "Default")
      (node (ref "C3") (pin "2") (pinfunction "2_2") (pintype "passive"))
      (node (ref "Q3") (pin "3") (pinfunction "S_3") (pintype "passive"))
      (node (ref "Q6") (pin "2") (pinfunction "D_2") (pintype "passive"))
      (node (ref "R4") (pin "2") (pinfunction "2_2") (pintype "passive"))
      (node (ref "U3") (pin "12") (pinfunction "VS3_12") (pintype "passive"))
      (node (ref "U4") (pin "2") (pinfunction "IN+_2") (pintype "passive"))
    )
    (net (code "125") (name "AGND") (class "Default")
      (node (ref "C4") (pin "1") (pinfunction "1_1") (pintype "passive"))
      (node (ref "C5") (pin "1") (pinfunction "1_1") (pintype "passive"))
      (node (ref "C8") (pin "1") (pinfunction "1_1") (pintype "passive"))
      (node (ref "R3") (pin "1") (pinfunction "1_1") (pintype "passive"))
      (node (ref "U1") (pin "1") (pinfunction "NC_1") (pintype "passive"))
      (node (ref "U1") (pin "4") (pinfunction "GND_4") (pintype "passive"))
      (node (ref "U1") (pin "7") (pinfunction "REF1_7") (pintype "passive"))
      (node (ref "U2") (pin "1") (pinfunction "NC_1") (pintype "passive"))
      (node (ref "U2") (pin "4") (pinfunction "GND_4") (pintype "passive"))
      (node (ref "U2") (pin "7") (pinfunction "REF1_7") (pintype "passive"))
      (node (ref "U4") (pin "1") (pinfunction "NC_1") (pintype "passive"))
      (node (ref "U4") (pin "4") (pinfunction "GND_4") (pintype "passive"))
      (node (ref "U4") (pin "7") (pinfunction "REF1_7") (pintype "passive"))
    )
    (net (code "126") (name "GND") (class "Default")
      (node (ref "C10") (pin "2") (pinfunction "2_2") (pintype "passive"))
      (node (ref "C11") (pin "2") (pinfunction "2_2") (pintype "passive"))
      (node (ref "C6") (pin "2") (pinfunction "2_2") (pintype "passive"))
      (node (ref "C7") (pin "2") (pinfunction "2_2") (pintype "passive"))
      (node (ref "C9") (pin "1") (pinfunction "1_1") (pintype "passive"))
      (node (ref "D4") (pin "2") (pinfunction "2_2") (pintype "passive"))
      (node (ref "E1") (pin "2") (pinfunction "K_2") (pintype "passive"))
      (node (ref "E2") (pin "2") (pinfunction "K_2") (pintype "passive"))
      (node (ref "E3") (pin "2") (pinfunction "K_2") (pintype "passive"))
      (node (ref "E4") (pin "2") (pinfunction "K_2") (pintype "passive"))
      (node (ref "E5") (pin "2") (pinfunction "K_2") (pintype "passive"))
      (node (ref "E6") (pin "2") (pinfunction "K_2") (pintype "passive"))
      (node (ref "E7") (pin "2") (pinfunction "K_2") (pintype "passive"))
      (node (ref "JP11") (pin "3") (pinfunction "3_3") (pintype "passive"))
      (node (ref "JP12") (pin "1") (pinfunction "1_1") (pintype "passive"))
      (node (ref "JP12") (pin "3") (pinfunction "3_3") (pintype "passive"))
      (node (ref "JP13") (pin "1") (pinfunction "1_1") (pintype "passive"))
      (node (ref "JP13") (pin "3") (pinfunction "3_3") (pintype "passive"))
      (node (ref "JP14") (pin "17") (pinfunction "17_17") (pintype "passive"))
      (node (ref "JP14") (pin "19") (pinfunction "19_19") (pintype "passive"))
      (node (ref "JP14") (pin "21") (pinfunction "21_21") (pintype "passive"))
      (node (ref "JP14") (pin "23") (pinfunction "23_23") (pintype "passive"))
      (node (ref "JP15") (pin "21") (pinfunction "21_21") (pintype "passive"))
      (node (ref "JP15") (pin "23") (pinfunction "23_23") (pintype "passive"))
      (node (ref "JP3") (pin "1") (pinfunction "1_1") (pintype "passive"))
      (node (ref "JP4") (pin "1") (pinfunction "1_1") (pintype "passive"))
      (node (ref "JP4") (pin "2") (pinfunction "2_2") (pintype "passive"))
      (node (ref "JP5") (pin "1") (pinfunction "1_1") (pintype "passive"))
      (node (ref "JP5") (pin "2") (pinfunction "2_2") (pintype "passive"))
      (node (ref "JP6") (pin "1") (pinfunction "1_1") (pintype "passive"))
      (node (ref "JP7") (pin "2") (pinfunction "2_2") (pintype "passive"))
      (node (ref "JP8") (pin "2") (pinfunction "2_2") (pintype "passive"))
      (node (ref "LED2") (pin "2") (pinfunction "K_2") (pintype "passive"))
      (node (ref "Q4") (pin "3") (pinfunction "S_3") (pintype "passive"))
      (node (ref "Q5") (pin "3") (pinfunction "S_3") (pintype "passive"))
      (node (ref "Q6") (pin "3") (pinfunction "S_3") (pintype "passive"))
      (node (ref "R3") (pin "2") (pinfunction "2_2") (pintype "passive"))
      (node (ref "R8") (pin "2") (pinfunction "2_2") (pintype "passive"))
      (node (ref "SW1") (pin "1") (pinfunction "1_1") (pintype "passive"))
      (node (ref "SW1") (pin "4") (pinfunction "4_4") (pintype "passive"))
      (node (ref "SW2") (pin "1") (pinfunction "1_1") (pintype "passive"))
      (node (ref "SW2") (pin "4") (pinfunction "4_4") (pintype "passive"))
      (node (ref "U3") (pin "8") (pinfunction "COM_8") (pintype "passive"))
    )
    (net (code "127") (name "Net-(D1-K)") (class "Default")
      (node (ref "C1") (pin "1") (pinfunction "1_1") (pintype "passive"))
      (node (ref "D1") (pin "2") (pinfunction "K_2") (pintype "passive"))
      (node (ref "U3") (pin "20") (pinfunction "VB1_20") (pintype "passive"))
    )
    (net (code "128") (name "Net-(D2-K)") (class "Default")
      (node (ref "C2") (pin "1") (pinfunction "1_1") (pintype "passive"))
      (node (ref "D2") (pin "2") (pinfunction "K_2") (pintype "passive"))
      (node (ref "U3") (pin "17") (pinfunction "VB2_17") (pintype "passive"))
    )
    (net (code "129") (name "Net-(D3-K)") (class "Default")
      (node (ref "C3") (pin "1") (pinfunction "1_1") (pintype "passive"))
      (node (ref "D3") (pin "2") (pinfunction "K_2") (pintype "passive"))
      (node (ref "U3") (pin "14") (pinfunction "VB3_14") (pintype "passive"))
    )
    (net (code "130") (name "Net-(LED1-A)") (class "Default")
      (node (ref "LED1") (pin "1") (pinfunction "A_1") (pintype "passive"))
      (node (ref "R17") (pin "1") (pinfunction "1_1") (pintype "passive"))
    )
    (net (code "131") (name "Net-(LED2-A)") (class "Default")
      (node (ref "LED2") (pin "1") (pinfunction "A_1") (pintype "passive"))
      (node (ref "R18") (pin "2") (pinfunction "2_2") (pintype "passive"))
    )
    (net (code "132") (name "Net-(Q1-G)") (class "Default")
      (node (ref "Q1") (pin "1") (pinfunction "G_1") (pintype "passive"))
      (node (ref "R9") (pin "1") (pinfunction "1_1") (pintype "passive"))
    )
    (net (code "133") (name "Net-(Q2-G)") (class "Default")
      (node (ref "Q2") (pin "1") (pinfunction "G_1") (pintype "passive"))
      (node (ref "R10") (pin "1") (pinfunction "1_1") (pintype "passive"))
    )
    (net (code "134") (name "Net-(Q3-G)") (class "Default")
      (node (ref "Q3") (pin "1") (pinfunction "G_1") (pintype "passive"))
      (node (ref "R11") (pin "1") (pinfunction "1_1") (pintype "passive"))
    )
    (net (code "135") (name "Net-(Q4-G)") (class "Default")
      (node (ref "Q4") (pin "1") (pinfunction "G_1") (pintype "passive"))
      (node (ref "R12") (pin "1") (pinfunction "1_1") (pintype "passive"))
    )
    (net (code "136") (name "Net-(Q5-G)") (class "Default")
      (node (ref "Q5") (pin "1") (pinfunction "G_1") (pintype "passive"))
      (node (ref "R13") (pin "1") (pinfunction "1_1") (pintype "passive"))
    )
    (net (code "137") (name "Net-(Q6-G)") (class "Default")
      (node (ref "Q6") (pin "1") (pinfunction "G_1") (pintype "passive"))
      (node (ref "R14") (pin "1") (pinfunction "1_1") (pintype "passive"))
    )
    (net (code "138") (name "PWR") (class "Default")
      (node (ref "*1") (pin "1") (pinfunction "1_1") (pintype "passive"))
      (node (ref "E1") (pin "1") (pinfunction "A_1") (pintype "passive"))
      (node (ref "E2") (pin "1") (pinfunction "A_1") (pintype "passive"))
      (node (ref "E3") (pin "1") (pinfunction "A_1") (pintype "passive"))
      (node (ref "E4") (pin "1") (pinfunction "A_1") (pintype "passive"))
      (node (ref "E5") (pin "1") (pinfunction "A_1") (pintype "passive"))
      (node (ref "E6") (pin "1") (pinfunction "A_1") (pintype "passive"))
      (node (ref "Q1") (pin "2") (pinfunction "D_2") (pintype "passive"))
      (node (ref "Q2") (pin "2") (pinfunction "D_2") (pintype "passive"))
      (node (ref "Q3") (pin "2") (pinfunction "D_2") (pintype "passive"))
      (node (ref "R7") (pin "1") (pinfunction "1_1") (pintype "passive"))
    )
    (net (code "139") (name "unconnected-(JP11-Pad4)") (class "Default")
      (node (ref "JP11") (pin "4") (pinfunction "4_4") (pintype "passive"))
    )
    (net (code "140") (name "unconnected-(JP12-Pad2)") (class "Default")
      (node (ref "JP12") (pin "2") (pinfunction "2_2") (pintype "passive"))
    )
    (net (code "141") (name "unconnected-(JP13-Pad2)") (class "Default")
      (node (ref "JP13") (pin "2") (pinfunction "2_2") (pintype "passive"))
    )
    (net (code "142") (name "unconnected-(JP13-Pad4)") (class "Default")
      (node (ref "JP13") (pin "4") (pinfunction "4_4") (pintype "passive"))
    )
    (net (code "143") (name "unconnected-(JP14-Pad18)") (class "Default")
      (node (ref "JP14") (pin "18") (pinfunction "18_18") (pintype "passive"))
    )
    (net (code "144") (name "unconnected-(JP14-Pad20)") (class "Default")
      (node (ref "JP14") (pin "20") (pinfunction "20_20") (pintype "passive"))
    )
    (net (code "145") (name "unconnected-(JP14-Pad22)") (class "Default")
      (node (ref "JP14") (pin "22") (pinfunction "22_22") (pintype "passive"))
    )
    (net (code "146") (name "unconnected-(JP15-Pad22)") (class "Default")
      (node (ref "JP15") (pin "22") (pinfunction "22_22") (pintype "passive"))
    )
    (net (code "147") (name "unconnected-(JP15-Pad24)") (class "Default")
      (node (ref "JP15") (pin "24") (pinfunction "24_24") (pintype "passive"))
    )
    (net (code "148") (name "unconnected-(S1-Pad1)") (class "Default")
      (node (ref "S1") (pin "1") (pinfunction "1_1") (pintype "passive"))
    )
  )
)
